# PCA9685.net
KiCad netlist of a schematic drawn in EAGLE
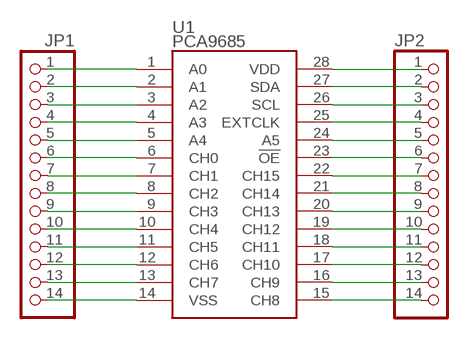
[diagram p0: schematic, sheet 1]

(export (version "E")
  (design (tool "Eeschema 10.0.6"))
  (components
    (comp (ref "JP1")
      (value "PINHD-1X14ROUND")
      (footprint "eagle-import:1X14_ROUND")
      (libsource (lib "eagle-import") (part "PINHD-1X14ROUND"))
    )
    (comp (ref "JP2")
      (value "PINHD-1X14ROUND")
      (footprint "eagle-import:1X14_ROUND")
      (libsource (lib "eagle-import") (part "PINHD-1X14ROUND"))
    )
    (comp (ref "U1")
      (value "PCA9685")
      (footprint "eagle-import:TSSOP-28_4MM")
      (libsource (lib "eagle-import") (part "PCA9685"))
    )
  )
  (nets
    (net (code "1") (name "Net-(U1-A0)") (class "Default")
      (node (ref "JP1") (pin "1") (pinfunction "1_1") (pintype "passive"))
      (node (ref "U1") (pin "1") (pinfunction "A0_1") (pintype "bidirectional"))
    )
    (net (code "2") (name "Net-(U1-A1)") (class "Default")
      (node (ref "JP1") (pin "2") (pinfunction "2_2") (pintype "passive"))
      (node (ref "U1") (pin "2") (pinfunction "A1_2") (pintype "bidirectional"))
    )
    (net (code "3") (name "Net-(U1-A2)") (class "Default")
      (node (ref "JP1") (pin "3") (pinfunction "3_3") (pintype "passive"))
      (node (ref "U1") (pin "3") (pinfunction "A2_3") (pintype "bidirectional"))
    )
    (net (code "4") (name "Net-(U1-A3)") (class "Default")
      (node (ref "JP1") (pin "4") (pinfunction "4_4") (pintype "passive"))
      (node (ref "U1") (pin "4") (pinfunction "A3_4") (pintype "bidirectional"))
    )
    (net (code "5") (name "Net-(U1-A4)") (class "Default")
      (node (ref "JP1") (pin "5") (pinfunction "5_5") (pintype "passive"))
      (node (ref "U1") (pin "5") (pinfunction "A4_5") (pintype "bidirectional"))
    )
    (net (code "6") (name "Net-(U1-A5)") (class "Default")
      (node (ref "JP2") (pin "5") (pinfunction "5_5") (pintype "passive"))
      (node (ref "U1") (pin "24") (pinfunction "A5_24") (pintype "bidirectional"))
    )
    (net (code "7") (name "Net-(U1-CH0)") (class "Default")
      (node (ref "JP1") (pin "6") (pinfunction "6_6") (pintype "passive"))
      (node (ref "U1") (pin "6") (pinfunction "CH0_6") (pintype "bidirectional"))
    )
    (net (code "8") (name "Net-(U1-CH1)") (class "Default")
      (node (ref "JP1") (pin "7") (pinfunction "7_7") (pintype "passive"))
      (node (ref "U1") (pin "7") (pinfunction "CH1_7") (pintype "bidirectional"))
    )
    (net (code "9") (name "Net-(U1-CH2)") (class "Default")
      (node (ref "JP1") (pin "8") (pinfunction "8_8") (pintype "passive"))
      (node (ref "U1") (pin "8") (pinfunction "CH2_8") (pintype "bidirectional"))
    )
    (net (code "10") (name "Net-(U1-CH3)") (class "Default")
      (node (ref "JP1") (pin "9") (pinfunction "9_9") (pintype "passive"))
      (node (ref "U1") (pin "9") (pinfunction "CH3_9") (pintype "bidirectional"))
    )
    (net (code "11") (name "Net-(U1-CH4)") (class "Default")
      (node (ref "JP1") (pin "10") (pinfunction "10_10") (pintype "passive"))
      (node (ref "U1") (pin "10") (pinfunction "CH4_10") (pintype "bidirectional"))
    )
    (net (code "12") (name "Net-(U1-CH5)") (class "Default")
      (node (ref "JP1") (pin "11") (pinfunction "11_11") (pintype "passive"))
      (node (ref "U1") (pin "11") (pinfunction "CH5_11") (pintype "bidirectional"))
    )
    (net (code "13") (name "Net-(U1-CH6)") (class "Default")
      (node (ref "JP1") (pin "12") (pinfunction "12_12") (pintype "passive"))
      (node (ref "U1") (pin "12") (pinfunction "CH6_12") (pintype "bidirectional"))
    )
    (net (code "14") (name "Net-(U1-CH7)") (class "Default")
      (node (ref "JP1") (pin "13") (pinfunction "13_13") (pintype "passive"))
      (node (ref "U1") (pin "13") (pinfunction "CH7_13") (pintype "bidirectional"))
    )
    (net (code "15") (name "Net-(U1-CH8)") (class "Default")
      (node (ref "JP2") (pin "14") (pinfunction "14_14") (pintype "passive"))
      (node (ref "U1") (pin "15") (pinfunction "CH8_15") (pintype "bidirectional"))
    )
    (net (code "16") (name "Net-(U1-CH9)") (class "Default")
      (node (ref "JP2") (pin "13") (pinfunction "13_13") (pintype "passive"))
      (node (ref "U1") (pin "16") (pinfunction "CH9_16") (pintype "bidirectional"))
    )
    (net (code "17") (name "Net-(U1-CH10)") (class "Default")
      (node (ref "JP2") (pin "12") (pinfunction "12_12") (pintype "passive"))
      (node (ref "U1") (pin "17") (pinfunction "CH10_17") (pintype "bidirectional"))
    )
    (net (code "18") (name "Net-(U1-CH11)") (class "Default")
      (node (ref "JP2") (pin "11") (pinfunction "11_11") (pintype "passive"))
      (node (ref "U1") (pin "18") (pinfunction "CH11_18") (pintype "bidirectional"))
    )
    (net (code "19") (name "Net-(U1-CH12)") (class "Default")
      (node (ref "JP2") (pin "10") (pinfunction "10_10") (pintype "passive"))
      (node (ref "U1") (pin "19") (pinfunction "CH12_19") (pintype "bidirectional"))
    )
    (net (code "20") (name "Net-(U1-CH13)") (class "Default")
      (node (ref "JP2") (pin "9") (pinfunction "9_9") (pintype "passive"))
      (node (ref "U1") (pin "20") (pinfunction "CH13_20") (pintype "bidirectional"))
    )
    (net (code "21") (name "Net-(U1-CH14)") (class "Default")
      (node (ref "JP2") (pin "8") (pinfunction "8_8") (pintype "passive"))
      (node (ref "U1") (pin "21") (pinfunction "CH14_21") (pintype "bidirectional"))
    )
    (net (code "22") (name "Net-(U1-CH15)") (class "Default")
      (node (ref "JP2") (pin "7") (pinfunction "7_7") (pintype "passive"))
      (node (ref "U1") (pin "22") (pinfunction "CH15_22") (pintype "bidirectional"))
    )
    (net (code "23") (name "Net-(U1-EXTCLK)") (class "Default")
      (node (ref "JP2") (pin "4") (pinfunction "4_4") (pintype "passive"))
      (node (ref "U1") (pin "25") (pinfunction "EXTCLK_25") (pintype "bidirectional"))
    )
    (net (code "24") (name "Net-(U1-SCL)") (class "Default")
      (node (ref "JP2") (pin "3") (pinfunction "3_3") (pintype "passive"))
      (node (ref "U1") (pin "26") (pinfunction "SCL_26") (pintype "bidirectional"))
    )
    (net (code "25") (name "Net-(U1-SDA)") (class "Default")
      (node (ref "JP2") (pin "2") (pinfunction "2_2") (pintype "passive"))
      (node (ref "U1") (pin "27") (pinfunction "SDA_27") (pintype "bidirectional"))
    )
    (net (code "26") (name "Net-(U1-VDD)") (class "Default")
      (node (ref "JP2") (pin "1") (pinfunction "1_1") (pintype "passive"))
      (node (ref "U1") (pin "28") (pinfunction "VDD_28") (pintype "bidirectional"))
    )
    (net (code "27") (name "Net-(U1-VSS)") (class "Default")
      (node (ref "JP1") (pin "14") (pinfunction "14_14") (pintype "passive"))
      (node (ref "U1") (pin "14") (pinfunction "VSS_14") (pintype "bidirectional"))
    )
    (net (code "28") (name "Net-(U1-~{OE})") (class "Default")
      (node (ref "JP2") (pin "6") (pinfunction "6_6") (pintype "passive"))
      (node (ref "U1") (pin "23") (pinfunction "~{OE}_23") (pintype "bidirectional"))
    )
  )
)
